# SPDT_FET_SW.net
KiCad netlist of a schematic drawn in Altium Designer
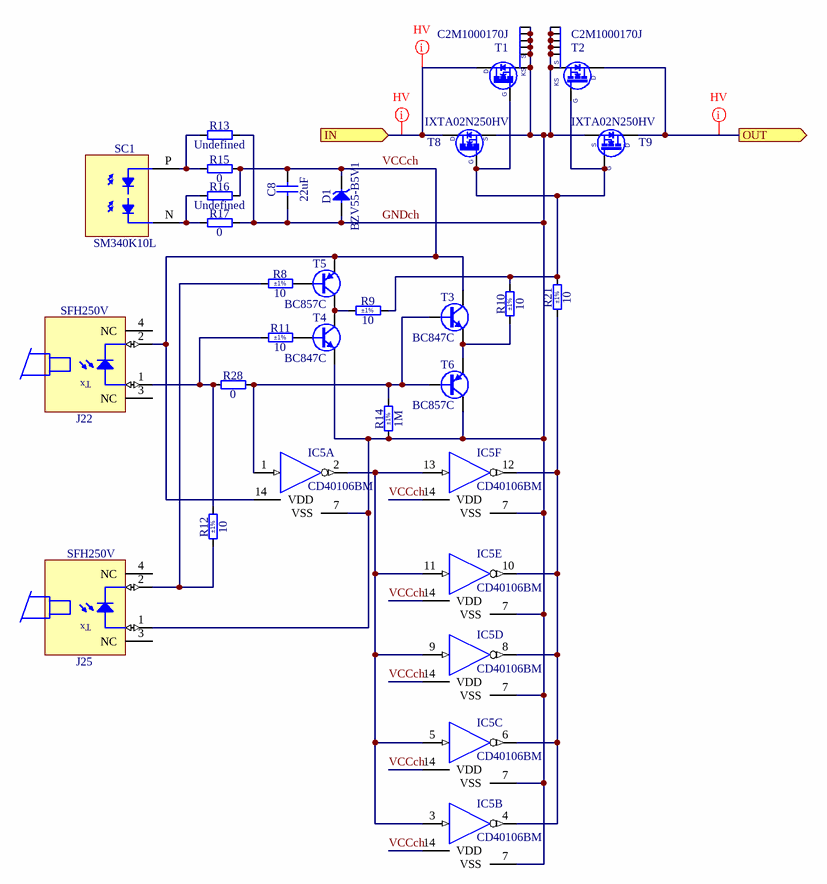
[diagram p0: SPDT_FET_SW.SchDoc]

(export (version "E")
  (design (tool "Eeschema 10.0.6"))
  (components
    (comp (ref "C8")
      (value "22uF")
      (footprint "CAPC2012X145N")
      (description "Non-polarised capacitor")
      (fields
        (field (name "PART NUMBER") "CC0805_22UF_25V_20%_X5R")
        (field (name "VOLTAGE") "25V")
        (field (name "AUTHOR") "CERN DEM WB")
      )
      (libsource (lib "Capacitors") (part "Capacitor - non polarized"))
    )
    (comp (ref "D1")
      (value "BZV55-B5V1")
      (footprint "DIOMELF3515N")
      (description "Zener Diode")
      (fields
        (field (name "VOLTAGE") "5V1")
        (field (name "POWER") "500mW")
        (field (name "AUTHOR") "CERN DEM JLC")
      )
      (libsource (lib "ICs And Semiconductors") (part "Diode Zener"))
    )
    (comp (ref "IC5")
      (value "CD40106BM")
      (footprint "SOIC127P600X175-14N")
      (description "Hex Inverting Schmitt-Trigger")
      (fields (field (name "MANUFACTURER") "TEXAS INSTRUMENTS") (field (name "AUTHOR") "CERN DEM JLC"))
      (libsource (lib "ICs And Semiconductors") (part "40106"))
    )
    (comp (ref "J22")
      (value "SFH250V")
      (footprint "SFH250V")
      (description "Plastic Connector Housing For Plastic Fiber Optic Photodiode Detector")
      (fields
        (field (name "MANUFACTURER") "AVAGO TECHNOLOGIES")
        (field (name "MANUFACTURER PART NUMBER") "SFH250V or SP000063852")
        (field (name "AUTHOR") "CERN DEM JLC")
      )
      (libsource (lib "Connectors") (part "SFH250V"))
    )
    (comp (ref "J25")
      (value "SFH250V")
      (footprint "SFH250V")
      (description "Plastic Connector Housing For Plastic Fiber Optic Photodiode Detector")
      (fields
        (field (name "MANUFACTURER") "AVAGO TECHNOLOGIES")
        (field (name "MANUFACTURER PART NUMBER") "SFH250V or SP000063852")
        (field (name "AUTHOR") "CERN DEM JLC")
      )
      (libsource (lib "Connectors") (part "SFH250V"))
    )
    (comp (ref "R8")
      (value "10")
      (footprint "RESC1608X55N")
      (description "Resistor - 1%")
      (fields
        (field (name "TOLERANCE") "±1%")
        (field (name "PART NUMBER") "R0603_10R_1%_0.1W_200PPM")
        (field (name "POWER") "0.1W")
        (field (name "AUTHOR") "CERN DEM JLC")
      )
      (libsource (lib "Resistors") (part "Resistor - 1%"))
    )
    (comp (ref "R9")
      (value "10")
      (footprint "RESC1608X55N")
      (description "Resistor - 1%")
      (fields
        (field (name "TOLERANCE") "±1%")
        (field (name "PART NUMBER") "R0603_10R_1%_0.1W_200PPM")
        (field (name "POWER") "0.1W")
        (field (name "AUTHOR") "CERN DEM JLC")
      )
      (libsource (lib "Resistors") (part "Resistor - 1%"))
    )
    (comp (ref "R10")
      (value "10")
      (footprint "RESC1608X55N")
      (description "Resistor - 1%")
      (fields
        (field (name "TOLERANCE") "±1%")
        (field (name "PART NUMBER") "R0603_10R_1%_0.1W_200PPM")
        (field (name "POWER") "0.1W")
        (field (name "AUTHOR") "CERN DEM JLC")
      )
      (libsource (lib "Resistors") (part "Resistor - 1%"))
    )
    (comp (ref "R11")
      (value "10")
      (footprint "RESC1608X55N")
      (description "Resistor - 1%")
      (fields
        (field (name "TOLERANCE") "±1%")
        (field (name "PART NUMBER") "R0603_10R_1%_0.1W_200PPM")
        (field (name "POWER") "0.1W")
        (field (name "AUTHOR") "CERN DEM JLC")
      )
      (libsource (lib "Resistors") (part "Resistor - 1%"))
    )
    (comp (ref "R12")
      (value "10")
      (footprint "RESC1608X55N")
      (description "Resistor - 1%")
      (fields
        (field (name "TOLERANCE") "±1%")
        (field (name "PART NUMBER") "R0603_10R_1%_0.1W_200PPM")
        (field (name "POWER") "0.1W")
        (field (name "AUTHOR") "CERN DEM JLC")
      )
      (libsource (lib "Resistors") (part "Resistor - 1%"))
    )
    (comp (ref "R13")
      (value "Undefined")
      (footprint "RESC1608X55N")
      (description "Resistor")
      (fields (field (name "PART NUMBER") "R0603_NO-VALUE") (field (name "AUTHOR") "CERN DEM JLC"))
      (libsource (lib "Resistors") (part "Resistor"))
    )
    (comp (ref "R14")
      (value "1M")
      (footprint "RESC1005X40N")
      (description "Resistor - 1%")
      (fields
        (field (name "TOLERANCE") "±1%")
        (field (name "PART NUMBER") "R0402_1M_1%_0.0625W_100PPM")
        (field (name "POWER") "0.0625W")
        (field (name "AUTHOR") "CERN DEM JLC")
      )
      (libsource (lib "Resistors") (part "Resistor - 1%"))
    )
    (comp (ref "R15")
      (value "0")
      (footprint "RESC1608X55N")
      (description "Resistor")
      (fields
        (field (name "PART NUMBER") "R0603_0R_JUMPER")
        (field (name "MANUFACTURER") "GENERIC")
        (field (name "AUTHOR") "CERN DEM JLC")
      )
      (libsource (lib "Resistors") (part "Resistor"))
    )
    (comp (ref "R16")
      (value "Undefined")
      (footprint "RESC1608X55N")
      (description "Resistor")
      (fields (field (name "PART NUMBER") "R0603_NO-VALUE") (field (name "AUTHOR") "CERN DEM JLC"))
      (libsource (lib "Resistors") (part "Resistor"))
    )
    (comp (ref "R17")
      (value "0")
      (footprint "RESC1608X55N")
      (description "Resistor")
      (fields
        (field (name "PART NUMBER") "R0603_0R_JUMPER")
        (field (name "MANUFACTURER") "GENERIC")
        (field (name "AUTHOR") "CERN DEM JLC")
      )
      (libsource (lib "Resistors") (part "Resistor"))
    )
    (comp (ref "R21")
      (value "10")
      (footprint "RESC1608X55N")
      (description "Resistor - 1%")
      (fields
        (field (name "TOLERANCE") "±1%")
        (field (name "PART NUMBER") "R0603_10R_1%_0.1W_200PPM")
        (field (name "POWER") "0.1W")
        (field (name "AUTHOR") "CERN DEM JLC")
      )
      (libsource (lib "Resistors") (part "Resistor - 1%"))
    )
    (comp (ref "R28")
      (value "0")
      (footprint "RESC1608X55N")
      (description "Resistor")
      (fields
        (field (name "PART NUMBER") "R0603_0R_JUMPER")
        (field (name "MANUFACTURER") "GENERIC")
        (field (name "AUTHOR") "CERN DEM JLC")
      )
      (libsource (lib "Resistors") (part "Resistor"))
    )
    (comp (ref "SC1")
      (value "SM340K10L")
      (footprint "SM340K10L")
      (description "MONOCRYSTAL SOLAR CELL 73.5MW 6.91V")
      (fields (field (name "MANUFACTURER") "ANYSOLAR") (field (name "AUTHOR") "GK"))
      (libsource (lib "Diodes") (part "SOLAR_SM340K10L"))
    )
    (comp (ref "T1")
      (value "C2M1000170J")
      (footprint "WOLFSPEED_TO-263-7")
      (description "N-CHANNEL MOSFET WITH DIODE")
      (fields (field (name "MANUFACTURER") "WOLFSPEED") (field (name "AUTHOR") "CERN DEM HF"))
      (libsource (lib "ICs And Semiconductors") (part "N-MOSFET-D 1G 2KS 3S 4S 5S 6S 7S 8D"))
    )
    (comp (ref "T2")
      (value "C2M1000170J")
      (footprint "WOLFSPEED_TO-263-7")
      (description "N-CHANNEL MOSFET WITH DIODE")
      (fields (field (name "MANUFACTURER") "WOLFSPEED") (field (name "AUTHOR") "CERN DEM HF"))
      (libsource (lib "") (part "N-MOSFET-D 1G 2KS 3S 4S 5S 6S 7S 8D_1"))
    )
    (comp (ref "T3")
      (value "BC847C")
      (footprint "SOT95P240X110-3N")
      (description "NPN Transistor")
      (fields (field (name "MANUFACTURER") "INFINEON") (field (name "AUTHOR") "CERN DEM JLC"))
      (libsource (lib "ICs And Semiconductors") (part "NPN B1 E2 C3"))
    )
    (comp (ref "T4")
      (value "BC847C")
      (footprint "SOT95P240X110-3N")
      (description "NPN Transistor")
      (fields (field (name "MANUFACTURER") "INFINEON") (field (name "AUTHOR") "CERN DEM JLC"))
      (libsource (lib "ICs And Semiconductors") (part "NPN B1 E2 C3"))
    )
    (comp (ref "T5")
      (value "BC857C")
      (footprint "SOT95P240X110-3N")
      (description "PNP Transistor")
      (fields (field (name "MANUFACTURER") "INFINEON") (field (name "AUTHOR") "CERN DEM JLC"))
      (libsource (lib "ICs And Semiconductors") (part "PNP B1 E2 C3"))
    )
    (comp (ref "T6")
      (value "BC857C")
      (footprint "SOT95P240X110-3N")
      (description "PNP Transistor")
      (fields (field (name "MANUFACTURER") "INFINEON") (field (name "AUTHOR") "CERN DEM JLC"))
      (libsource (lib "ICs And Semiconductors") (part "PNP B1 E2 C3"))
    )
    (comp (ref "T8")
      (value "IXTA02N250HV")
      (footprint "IXYS_TO-263AB")
      (description "N-CHANNEL MOSFET WITH DIODE")
      (fields
        (field (name "MANUFACTURER") "IXYS")
        (field (name "MANUFACTURER PART NUMBER") "TO-263AB")
        (field (name "AUTHOR") "CERN DEM HF")
      )
      (libsource (lib "") (part "N-MOSFET-D 1G 2S 3D_1"))
    )
    (comp (ref "T9")
      (value "IXTA02N250HV")
      (footprint "IXYS_TO-263AB")
      (description "N-CHANNEL MOSFET WITH DIODE")
      (fields
        (field (name "MANUFACTURER") "IXYS")
        (field (name "MANUFACTURER PART NUMBER") "TO-263AB")
        (field (name "AUTHOR") "CERN DEM HF")
      )
      (libsource (lib "ICs And Semiconductors") (part "N-MOSFET-D 1G 2S 3D"))
    )
  )
  (nets
    (net (code "1") (name "/GNDch") (class "Default")
      (node (ref "C8") (pin "1") (pinfunction "1_1") (pintype "passive"))
      (node (ref "D1") (pin "2") (pinfunction "A_2") (pintype "passive"))
      (node (ref "IC5") (pin "7") (pinfunction "VSS_7") (pintype "power_in"))
      (node (ref "J25") (pin "1") (pinfunction "A_1") (pintype "bidirectional"))
      (node (ref "R13") (pin "2") (pinfunction "2_2") (pintype "passive"))
      (node (ref "R14") (pin "1") (pinfunction "1_1") (pintype "passive"))
      (node (ref "R17") (pin "2") (pinfunction "2_2") (pintype "passive"))
      (node (ref "T1") (pin "2") (pinfunction "S_2") (pintype "passive"))
      (node (ref "T1") (pin "3") (pinfunction "S_3") (pintype "passive"))
      (node (ref "T1") (pin "4") (pinfunction "S_4") (pintype "passive"))
      (node (ref "T1") (pin "5") (pinfunction "S_5") (pintype "passive"))
      (node (ref "T1") (pin "6") (pinfunction "S_6") (pintype "passive"))
      (node (ref "T1") (pin "7") (pinfunction "S_7") (pintype "passive"))
      (node (ref "T2") (pin "2") (pinfunction "S_2") (pintype "passive"))
      (node (ref "T2") (pin "3") (pinfunction "S_3") (pintype "passive"))
      (node (ref "T2") (pin "4") (pinfunction "S_4") (pintype "passive"))
      (node (ref "T2") (pin "5") (pinfunction "S_5") (pintype "passive"))
      (node (ref "T2") (pin "6") (pinfunction "S_6") (pintype "passive"))
      (node (ref "T2") (pin "7") (pinfunction "S_7") (pintype "passive"))
      (node (ref "T4") (pin "2") (pinfunction "E_2") (pintype "passive"))
      (node (ref "T6") (pin "3") (pinfunction "C_3") (pintype "passive"))
      (node (ref "T8") (pin "2") (pinfunction "S_2") (pintype "passive"))
      (node (ref "T9") (pin "2") (pinfunction "S_2") (pintype "passive"))
    )
    (net (code "2") (name "/IN") (class "Default")
      (node (ref "T1") (pin "8") (pinfunction "D_8") (pintype "passive"))
      (node (ref "T8") (pin "3") (pinfunction "D_3") (pintype "passive"))
    )
    (net (code "3") (name "/OUT") (class "Default")
      (node (ref "T2") (pin "8") (pinfunction "D_8") (pintype "passive"))
      (node (ref "T9") (pin "3") (pinfunction "D_3") (pintype "passive"))
    )
    (net (code "4") (name "/VCCch") (class "Default")
      (node (ref "C8") (pin "2") (pinfunction "2_2") (pintype "passive"))
      (node (ref "D1") (pin "1") (pinfunction "C_1") (pintype "passive"))
      (node (ref "IC5") (pin "14") (pinfunction "VDD_14") (pintype "power_in"))
      (node (ref "J22") (pin "2") (pinfunction "C_2") (pintype "bidirectional"))
      (node (ref "R15") (pin "2") (pinfunction "2_2") (pintype "passive"))
      (node (ref "R16") (pin "2") (pinfunction "2_2") (pintype "passive"))
      (node (ref "T3") (pin "3") (pinfunction "C_3") (pintype "passive"))
      (node (ref "T5") (pin "2") (pinfunction "E_2") (pintype "passive"))
    )
    (net (code "5") (name "Net-(IC5A-IN)") (class "Default")
      (node (ref "IC5") (pin "1") (pinfunction "IN_1") (pintype "input"))
      (node (ref "R14") (pin "2") (pinfunction "2_2") (pintype "passive"))
      (node (ref "R28") (pin "2") (pinfunction "2_2") (pintype "passive"))
      (node (ref "T3") (pin "1") (pinfunction "B_1") (pintype "passive"))
      (node (ref "T6") (pin "1") (pinfunction "B_1") (pintype "passive"))
    )
    (net (code "6") (name "Net-(IC5A-OUT)") (class "Default")
      (node (ref "IC5") (pin "11") (pinfunction "IN_11") (pintype "input"))
      (node (ref "IC5") (pin "13") (pinfunction "IN_13") (pintype "input"))
      (node (ref "IC5") (pin "2") (pinfunction "OUT_2") (pintype "output"))
      (node (ref "IC5") (pin "3") (pinfunction "IN_3") (pintype "input"))
      (node (ref "IC5") (pin "5") (pinfunction "IN_5") (pintype "input"))
      (node (ref "IC5") (pin "9") (pinfunction "IN_9") (pintype "input"))
    )
    (net (code "7") (name "Net-(IC5B-OUT)") (class "Default")
      (node (ref "IC5") (pin "10") (pinfunction "OUT_10") (pintype "output"))
      (node (ref "IC5") (pin "12") (pinfunction "OUT_12") (pintype "output"))
      (node (ref "IC5") (pin "4") (pinfunction "OUT_4") (pintype "output"))
      (node (ref "IC5") (pin "6") (pinfunction "OUT_6") (pintype "output"))
      (node (ref "IC5") (pin "8") (pinfunction "OUT_8") (pintype "output"))
      (node (ref "R21") (pin "1") (pinfunction "1_1") (pintype "passive"))
    )
    (net (code "8") (name "Net-(J22-A)") (class "Default")
      (node (ref "J22") (pin "1") (pinfunction "A_1") (pintype "bidirectional"))
      (node (ref "R11") (pin "1") (pinfunction "1_1") (pintype "passive"))
      (node (ref "R12") (pin "2") (pinfunction "2_2") (pintype "passive"))
      (node (ref "R28") (pin "1") (pinfunction "1_1") (pintype "passive"))
    )
    (net (code "9") (name "Net-(J25-C)") (class "Default")
      (node (ref "J25") (pin "2") (pinfunction "C_2") (pintype "bidirectional"))
      (node (ref "R12") (pin "1") (pinfunction "1_1") (pintype "passive"))
      (node (ref "R8") (pin "1") (pinfunction "1_1") (pintype "passive"))
    )
    (net (code "10") (name "Net-(R13-Pad1)") (class "Default")
      (node (ref "R13") (pin "1") (pinfunction "1_1") (pintype "passive"))
      (node (ref "R15") (pin "1") (pinfunction "1_1") (pintype "passive"))
      (node (ref "SC1") (pin "P") (pinfunction "P_P") (pintype "passive"))
    )
    (net (code "11") (name "Net-(R16-Pad1)") (class "Default")
      (node (ref "R16") (pin "1") (pinfunction "1_1") (pintype "passive"))
      (node (ref "R17") (pin "1") (pinfunction "1_1") (pintype "passive"))
      (node (ref "SC1") (pin "N") (pinfunction "N_N") (pintype "passive"))
    )
    (net (code "12") (name "Net-(T1-G)") (class "Default")
      (node (ref "R10") (pin "2") (pinfunction "2_2") (pintype "passive"))
      (node (ref "R21") (pin "2") (pinfunction "2_2") (pintype "passive"))
      (node (ref "R9") (pin "2") (pinfunction "2_2") (pintype "passive"))
      (node (ref "T1") (pin "1") (pinfunction "G_1") (pintype "passive"))
      (node (ref "T2") (pin "1") (pinfunction "G_1") (pintype "passive"))
      (node (ref "T8") (pin "1") (pinfunction "G_1") (pintype "passive"))
      (node (ref "T9") (pin "1") (pinfunction "G_1") (pintype "passive"))
    )
    (net (code "13") (name "Net-(T3-E)") (class "Default")
      (node (ref "R10") (pin "1") (pinfunction "1_1") (pintype "passive"))
      (node (ref "T3") (pin "2") (pinfunction "E_2") (pintype "passive"))
      (node (ref "T6") (pin "2") (pinfunction "E_2") (pintype "passive"))
    )
    (net (code "14") (name "Net-(T4-B)") (class "Default")
      (node (ref "R11") (pin "2") (pinfunction "2_2") (pintype "passive"))
      (node (ref "T4") (pin "1") (pinfunction "B_1") (pintype "passive"))
    )
    (net (code "15") (name "Net-(T4-C)") (class "Default")
      (node (ref "R9") (pin "1") (pinfunction "1_1") (pintype "passive"))
      (node (ref "T4") (pin "3") (pinfunction "C_3") (pintype "passive"))
      (node (ref "T5") (pin "3") (pinfunction "C_3") (pintype "passive"))
    )
    (net (code "16") (name "Net-(T5-B)") (class "Default")
      (node (ref "R8") (pin "2") (pinfunction "2_2") (pintype "passive"))
      (node (ref "T5") (pin "1") (pinfunction "B_1") (pintype "passive"))
    )
    (net (code "17") (name "unconnected-(J22-NC-Pad3)") (class "Default")
      (node (ref "J22") (pin "3") (pinfunction "NC_3") (pintype "passive"))
    )
    (net (code "18") (name "unconnected-(J22-NC-Pad4)") (class "Default")
      (node (ref "J22") (pin "4") (pinfunction "NC_4") (pintype "passive"))
    )
    (net (code "19") (name "unconnected-(J25-NC-Pad3)") (class "Default")
      (node (ref "J25") (pin "3") (pinfunction "NC_3") (pintype "passive"))
    )
    (net (code "20") (name "unconnected-(J25-NC-Pad4)") (class "Default")
      (node (ref "J25") (pin "4") (pinfunction "NC_4") (pintype "passive"))
    )
  )
)
